# OSSI-1_Side_Panel.net
KiCad netlist of a schematic drawn in EAGLE
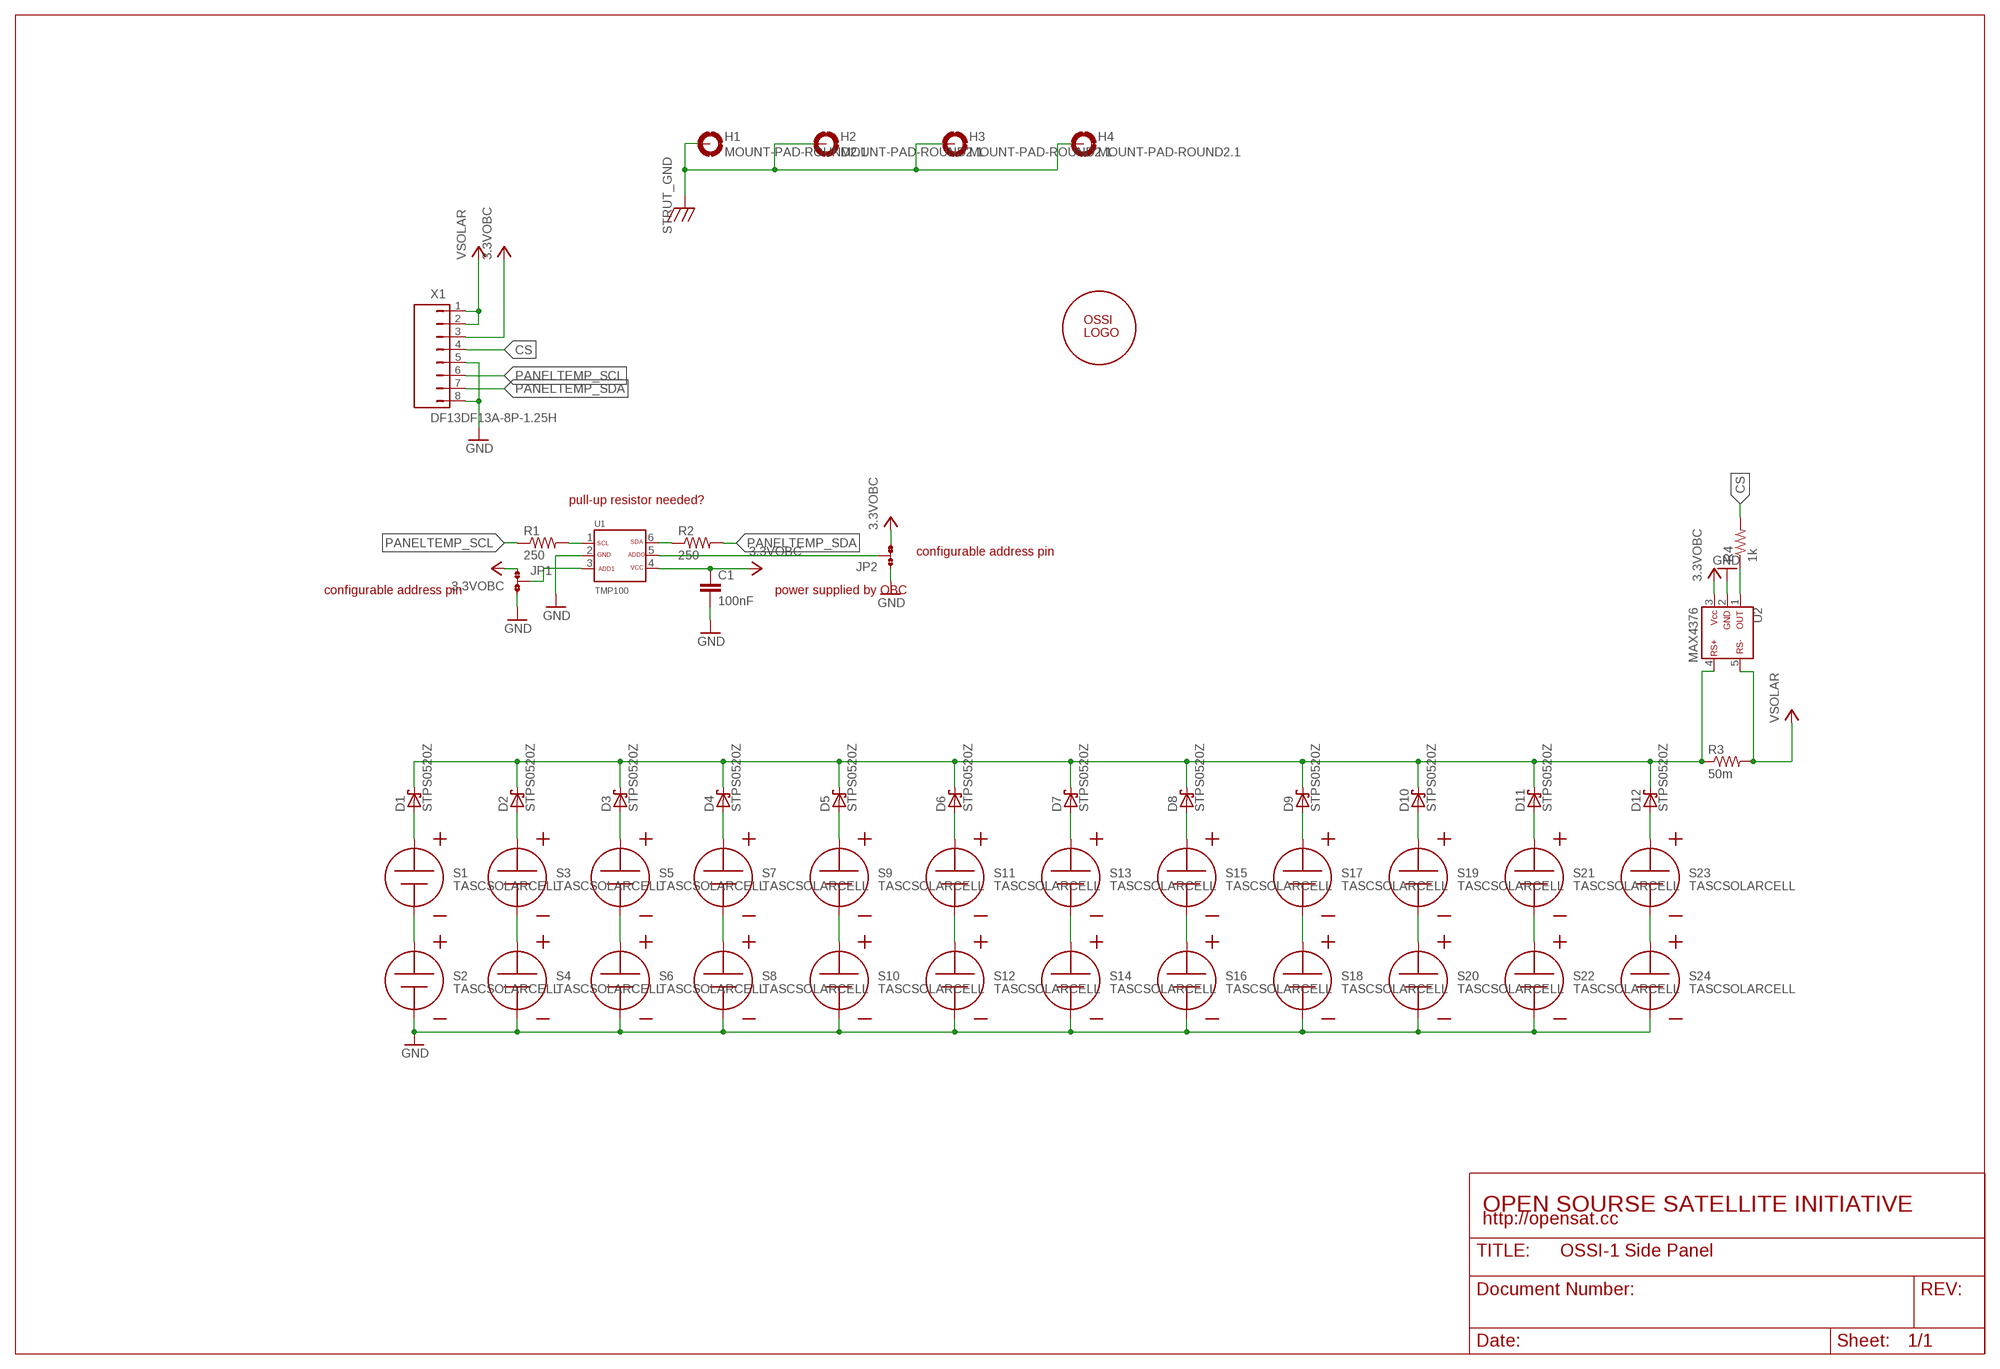
[diagram p0: schematic, sheet 1]

(export (version "E")
  (design (tool "Eeschema 10.0.6"))
  (components
    (comp (ref "C1")
      (value "100nF")
      (footprint "eagle-import:C0603(1608)")
      (libsource (lib "eagle-import") (part "C0603(1608)"))
    )
    (comp (ref "D1")
      (value "STPS0520Z")
      (footprint "eagle-import:SOD-123")
      (libsource (lib "eagle-import") (part "STPS0520Z"))
    )
    (comp (ref "D2")
      (value "STPS0520Z")
      (footprint "eagle-import:SOD-123")
      (libsource (lib "eagle-import") (part "STPS0520Z"))
    )
    (comp (ref "D3")
      (value "STPS0520Z")
      (footprint "eagle-import:SOD-123")
      (libsource (lib "eagle-import") (part "STPS0520Z"))
    )
    (comp (ref "D4")
      (value "STPS0520Z")
      (footprint "eagle-import:SOD-123")
      (libsource (lib "eagle-import") (part "STPS0520Z"))
    )
    (comp (ref "D5")
      (value "STPS0520Z")
      (footprint "eagle-import:SOD-123")
      (libsource (lib "eagle-import") (part "STPS0520Z"))
    )
    (comp (ref "D6")
      (value "STPS0520Z")
      (footprint "eagle-import:SOD-123")
      (libsource (lib "eagle-import") (part "STPS0520Z"))
    )
    (comp (ref "D7")
      (value "STPS0520Z")
      (footprint "eagle-import:SOD-123")
      (libsource (lib "eagle-import") (part "STPS0520Z"))
    )
    (comp (ref "D8")
      (value "STPS0520Z")
      (footprint "eagle-import:SOD-123")
      (libsource (lib "eagle-import") (part "STPS0520Z"))
    )
    (comp (ref "D9")
      (value "STPS0520Z")
      (footprint "eagle-import:SOD-123")
      (libsource (lib "eagle-import") (part "STPS0520Z"))
    )
    (comp (ref "D10")
      (value "STPS0520Z")
      (footprint "eagle-import:SOD-123")
      (libsource (lib "eagle-import") (part "STPS0520Z"))
    )
    (comp (ref "D11")
      (value "STPS0520Z")
      (footprint "eagle-import:SOD-123")
      (libsource (lib "eagle-import") (part "STPS0520Z"))
    )
    (comp (ref "D12")
      (value "STPS0520Z")
      (footprint "eagle-import:SOD-123")
      (libsource (lib "eagle-import") (part "STPS0520Z"))
    )
    (comp (ref "H1")
      (value "MOUNT-PAD-ROUND2.1")
      (footprint "eagle-import:2.1-PAD-ROUND")
      (libsource (lib "eagle-import") (part "MOUNT-PAD-ROUND2.1"))
    )
    (comp (ref "H2")
      (value "MOUNT-PAD-ROUND2.1")
      (footprint "eagle-import:2.1-PAD-ROUND")
      (libsource (lib "eagle-import") (part "MOUNT-PAD-ROUND2.1"))
    )
    (comp (ref "H3")
      (value "MOUNT-PAD-ROUND2.1")
      (footprint "eagle-import:2.1-PAD-ROUND")
      (libsource (lib "eagle-import") (part "MOUNT-PAD-ROUND2.1"))
    )
    (comp (ref "H4")
      (value "MOUNT-PAD-ROUND2.1")
      (footprint "eagle-import:2.1-PAD-ROUND")
      (libsource (lib "eagle-import") (part "MOUNT-PAD-ROUND2.1"))
    )
    (comp (ref "JP1")
      (value "JP2")
      (footprint "eagle-import:JP2SMD0603")
      (libsource (lib "eagle-import") (part "JP2"))
    )
    (comp (ref "JP2")
      (value "JP2")
      (footprint "eagle-import:JP2SMD0603")
      (libsource (lib "eagle-import") (part "JP2"))
    )
    (comp (ref "R1")
      (value "250")
      (footprint "eagle-import:R0603(1608)")
      (libsource (lib "eagle-import") (part "R0603(1608)"))
    )
    (comp (ref "R2")
      (value "250")
      (footprint "eagle-import:R0603(1608)")
      (libsource (lib "eagle-import") (part "R0603(1608)"))
    )
    (comp (ref "R3")
      (value "50m")
      (footprint "eagle-import:WSL1206")
      (libsource (lib "eagle-import") (part "RWSL1206"))
    )
    (comp (ref "R4")
      (value "1k")
      (footprint "eagle-import:R0603(1608)")
      (libsource (lib "eagle-import") (part "R0603(1608)"))
    )
    (comp (ref "S1")
      (value "TASCSOLARCELL")
      (footprint "eagle-import:TASCSOLARCELL")
      (libsource (lib "eagle-import") (part "TASCSOLARCELL"))
    )
    (comp (ref "S2")
      (value "TASCSOLARCELL")
      (footprint "eagle-import:TASCSOLARCELL")
      (libsource (lib "eagle-import") (part "TASCSOLARCELL"))
    )
    (comp (ref "S3")
      (value "TASCSOLARCELL")
      (footprint "eagle-import:TASCSOLARCELL")
      (libsource (lib "eagle-import") (part "TASCSOLARCELL"))
    )
    (comp (ref "S4")
      (value "TASCSOLARCELL")
      (footprint "eagle-import:TASCSOLARCELL")
      (libsource (lib "eagle-import") (part "TASCSOLARCELL"))
    )
    (comp (ref "S5")
      (value "TASCSOLARCELL")
      (footprint "eagle-import:TASCSOLARCELL")
      (libsource (lib "eagle-import") (part "TASCSOLARCELL"))
    )
    (comp (ref "S6")
      (value "TASCSOLARCELL")
      (footprint "eagle-import:TASCSOLARCELL")
      (libsource (lib "eagle-import") (part "TASCSOLARCELL"))
    )
    (comp (ref "S7")
      (value "TASCSOLARCELL")
      (footprint "eagle-import:TASCSOLARCELL")
      (libsource (lib "eagle-import") (part "TASCSOLARCELL"))
    )
    (comp (ref "S8")
      (value "TASCSOLARCELL")
      (footprint "eagle-import:TASCSOLARCELL")
      (libsource (lib "eagle-import") (part "TASCSOLARCELL"))
    )
    (comp (ref "S9")
      (value "TASCSOLARCELL")
      (footprint "eagle-import:TASCSOLARCELL")
      (libsource (lib "eagle-import") (part "TASCSOLARCELL"))
    )
    (comp (ref "S10")
      (value "TASCSOLARCELL")
      (footprint "eagle-import:TASCSOLARCELL")
      (libsource (lib "eagle-import") (part "TASCSOLARCELL"))
    )
    (comp (ref "S11")
      (value "TASCSOLARCELL")
      (footprint "eagle-import:TASCSOLARCELL")
      (libsource (lib "eagle-import") (part "TASCSOLARCELL"))
    )
    (comp (ref "S12")
      (value "TASCSOLARCELL")
      (footprint "eagle-import:TASCSOLARCELL")
      (libsource (lib "eagle-import") (part "TASCSOLARCELL"))
    )
    (comp (ref "S13")
      (value "TASCSOLARCELL")
      (footprint "eagle-import:TASCSOLARCELL")
      (libsource (lib "eagle-import") (part "TASCSOLARCELL"))
    )
    (comp (ref "S14")
      (value "TASCSOLARCELL")
      (footprint "eagle-import:TASCSOLARCELL")
      (libsource (lib "eagle-import") (part "TASCSOLARCELL"))
    )
    (comp (ref "S15")
      (value "TASCSOLARCELL")
      (footprint "eagle-import:TASCSOLARCELL")
      (libsource (lib "eagle-import") (part "TASCSOLARCELL"))
    )
    (comp (ref "S16")
      (value "TASCSOLARCELL")
      (footprint "eagle-import:TASCSOLARCELL")
      (libsource (lib "eagle-import") (part "TASCSOLARCELL"))
    )
    (comp (ref "S17")
      (value "TASCSOLARCELL")
      (footprint "eagle-import:TASCSOLARCELL")
      (libsource (lib "eagle-import") (part "TASCSOLARCELL"))
    )
    (comp (ref "S18")
      (value "TASCSOLARCELL")
      (footprint "eagle-import:TASCSOLARCELL")
      (libsource (lib "eagle-import") (part "TASCSOLARCELL"))
    )
    (comp (ref "S19")
      (value "TASCSOLARCELL")
      (footprint "eagle-import:TASCSOLARCELL")
      (libsource (lib "eagle-import") (part "TASCSOLARCELL"))
    )
    (comp (ref "S20")
      (value "TASCSOLARCELL")
      (footprint "eagle-import:TASCSOLARCELL")
      (libsource (lib "eagle-import") (part "TASCSOLARCELL"))
    )
    (comp (ref "S21")
      (value "TASCSOLARCELL")
      (footprint "eagle-import:TASCSOLARCELL")
      (libsource (lib "eagle-import") (part "TASCSOLARCELL"))
    )
    (comp (ref "S22")
      (value "TASCSOLARCELL")
      (footprint "eagle-import:TASCSOLARCELL")
      (libsource (lib "eagle-import") (part "TASCSOLARCELL"))
    )
    (comp (ref "S23")
      (value "TASCSOLARCELL")
      (footprint "eagle-import:TASCSOLARCELL")
      (libsource (lib "eagle-import") (part "TASCSOLARCELL"))
    )
    (comp (ref "S24")
      (value "TASCSOLARCELL")
      (footprint "eagle-import:TASCSOLARCELL")
      (libsource (lib "eagle-import") (part "TASCSOLARCELL"))
    )
    (comp (ref "U$2")
      (value "OSSILOGO")
      (footprint "eagle-import:OSSILOGORECT1005")
      (libsource (lib "eagle-import") (part "OSSILOGO"))
    )
    (comp (ref "U1")
      (value "TMP100")
      (footprint "eagle-import:SOT23-6DBV")
      (libsource (lib "eagle-import") (part "TMP100"))
    )
    (comp (ref "U2")
      (value "MAX4376")
      (footprint "eagle-import:SOT23-5DBV")
      (libsource (lib "eagle-import") (part "MAX4376"))
    )
    (comp (ref "X1")
      (value "DF13DF13A-8P-1.25H")
      (footprint "eagle-import:DF13A-8P")
      (libsource (lib "eagle-import") (part "DF13DF13A-8P-1.25H"))
    )
  )
  (nets
    (net (code "1") (name "3.3VOBC") (class "Default")
      (node (ref "C1") (pin "1") (pinfunction "1_1") (pintype "passive"))
      (node (ref "JP1") (pin "1") (pinfunction "1_1") (pintype "passive"))
      (node (ref "JP2") (pin "3") (pinfunction "3_3") (pintype "passive"))
      (node (ref "U1") (pin "4") (pinfunction "4_4") (pintype "bidirectional"))
      (node (ref "U2") (pin "3") (pinfunction "P$3_3") (pintype "power_in"))
      (node (ref "X1") (pin "3") (pinfunction "3_3") (pintype "passive"))
    )
    (net (code "2") (name "CS") (class "Default")
      (node (ref "R4") (pin "2") (pinfunction "2_2") (pintype "passive"))
      (node (ref "X1") (pin "4") (pinfunction "4_4") (pintype "passive"))
    )
    (net (code "3") (name "GND") (class "Default")
      (node (ref "C1") (pin "2") (pinfunction "2_2") (pintype "passive"))
      (node (ref "JP1") (pin "3") (pinfunction "3_3") (pintype "passive"))
      (node (ref "JP2") (pin "1") (pinfunction "1_1") (pintype "passive"))
      (node (ref "S10") (pin "N") (pinfunction "N_N") (pintype "power_in"))
      (node (ref "S12") (pin "N") (pinfunction "N_N") (pintype "power_in"))
      (node (ref "S14") (pin "N") (pinfunction "N_N") (pintype "power_in"))
      (node (ref "S16") (pin "N") (pinfunction "N_N") (pintype "power_in"))
      (node (ref "S18") (pin "N") (pinfunction "N_N") (pintype "power_in"))
      (node (ref "S2") (pin "N") (pinfunction "N_N") (pintype "power_in"))
      (node (ref "S20") (pin "N") (pinfunction "N_N") (pintype "power_in"))
      (node (ref "S22") (pin "N") (pinfunction "N_N") (pintype "power_in"))
      (node (ref "S24") (pin "N") (pinfunction "N_N") (pintype "power_in"))
      (node (ref "S4") (pin "N") (pinfunction "N_N") (pintype "power_in"))
      (node (ref "S6") (pin "N") (pinfunction "N_N") (pintype "power_in"))
      (node (ref "S8") (pin "N") (pinfunction "N_N") (pintype "power_in"))
      (node (ref "U1") (pin "2") (pinfunction "2_2") (pintype "bidirectional"))
      (node (ref "U2") (pin "2") (pinfunction "P$2_2") (pintype "power_in"))
      (node (ref "X1") (pin "5") (pinfunction "5_5") (pintype "passive"))
      (node (ref "X1") (pin "8") (pinfunction "8_8") (pintype "passive"))
    )
    (net (code "4") (name "Net-(D1-PadA)") (class "Default")
      (node (ref "D1") (pin "A") (pinfunction "A_A") (pintype "passive"))
      (node (ref "S1") (pin "P") (pinfunction "P_P") (pintype "power_in"))
    )
    (net (code "5") (name "Net-(D2-PadA)") (class "Default")
      (node (ref "D2") (pin "A") (pinfunction "A_A") (pintype "passive"))
      (node (ref "S3") (pin "P") (pinfunction "P_P") (pintype "power_in"))
    )
    (net (code "6") (name "Net-(D3-PadA)") (class "Default")
      (node (ref "D3") (pin "A") (pinfunction "A_A") (pintype "passive"))
      (node (ref "S5") (pin "P") (pinfunction "P_P") (pintype "power_in"))
    )
    (net (code "7") (name "Net-(D4-PadA)") (class "Default")
      (node (ref "D4") (pin "A") (pinfunction "A_A") (pintype "passive"))
      (node (ref "S7") (pin "P") (pinfunction "P_P") (pintype "power_in"))
    )
    (net (code "8") (name "Net-(D5-PadA)") (class "Default")
      (node (ref "D5") (pin "A") (pinfunction "A_A") (pintype "passive"))
      (node (ref "S9") (pin "P") (pinfunction "P_P") (pintype "power_in"))
    )
    (net (code "9") (name "Net-(D6-PadA)") (class "Default")
      (node (ref "D6") (pin "A") (pinfunction "A_A") (pintype "passive"))
      (node (ref "S11") (pin "P") (pinfunction "P_P") (pintype "power_in"))
    )
    (net (code "10") (name "Net-(D7-PadA)") (class "Default")
      (node (ref "D7") (pin "A") (pinfunction "A_A") (pintype "passive"))
      (node (ref "S13") (pin "P") (pinfunction "P_P") (pintype "power_in"))
    )
    (net (code "11") (name "Net-(D8-PadA)") (class "Default")
      (node (ref "D8") (pin "A") (pinfunction "A_A") (pintype "passive"))
      (node (ref "S15") (pin "P") (pinfunction "P_P") (pintype "power_in"))
    )
    (net (code "12") (name "Net-(D9-PadA)") (class "Default")
      (node (ref "D9") (pin "A") (pinfunction "A_A") (pintype "passive"))
      (node (ref "S17") (pin "P") (pinfunction "P_P") (pintype "power_in"))
    )
    (net (code "13") (name "Net-(D10-PadA)") (class "Default")
      (node (ref "D10") (pin "A") (pinfunction "A_A") (pintype "passive"))
      (node (ref "S19") (pin "P") (pinfunction "P_P") (pintype "power_in"))
    )
    (net (code "14") (name "Net-(D11-PadA)") (class "Default")
      (node (ref "D11") (pin "A") (pinfunction "A_A") (pintype "passive"))
      (node (ref "S21") (pin "P") (pinfunction "P_P") (pintype "power_in"))
    )
    (net (code "15") (name "Net-(D12-PadA)") (class "Default")
      (node (ref "D12") (pin "A") (pinfunction "A_A") (pintype "passive"))
      (node (ref "S23") (pin "P") (pinfunction "P_P") (pintype "power_in"))
    )
    (net (code "16") (name "Net-(JP1-Pad2)") (class "Default")
      (node (ref "JP1") (pin "2") (pinfunction "2_2") (pintype "passive"))
      (node (ref "U1") (pin "3") (pinfunction "3_3") (pintype "bidirectional"))
    )
    (net (code "17") (name "Net-(JP2-Pad2)") (class "Default")
      (node (ref "JP2") (pin "2") (pinfunction "2_2") (pintype "passive"))
      (node (ref "U1") (pin "5") (pinfunction "5_5") (pintype "bidirectional"))
    )
    (net (code "18") (name "Net-(R1-Pad2)") (class "Default")
      (node (ref "R1") (pin "2") (pinfunction "2_2") (pintype "passive"))
      (node (ref "U1") (pin "1") (pinfunction "1_1") (pintype "bidirectional"))
    )
    (net (code "19") (name "Net-(R2-Pad1)") (class "Default")
      (node (ref "R2") (pin "1") (pinfunction "1_1") (pintype "passive"))
      (node (ref "U1") (pin "6") (pinfunction "6_6") (pintype "bidirectional"))
    )
    (net (code "20") (name "Net-(R3-1)") (class "Default")
      (node (ref "D1") (pin "C") (pinfunction "C_C") (pintype "passive"))
      (node (ref "D10") (pin "C") (pinfunction "C_C") (pintype "passive"))
      (node (ref "D11") (pin "C") (pinfunction "C_C") (pintype "passive"))
      (node (ref "D12") (pin "C") (pinfunction "C_C") (pintype "passive"))
      (node (ref "D2") (pin "C") (pinfunction "C_C") (pintype "passive"))
      (node (ref "D3") (pin "C") (pinfunction "C_C") (pintype "passive"))
      (node (ref "D4") (pin "C") (pinfunction "C_C") (pintype "passive"))
      (node (ref "D5") (pin "C") (pinfunction "C_C") (pintype "passive"))
      (node (ref "D6") (pin "C") (pinfunction "C_C") (pintype "passive"))
      (node (ref "D7") (pin "C") (pinfunction "C_C") (pintype "passive"))
      (node (ref "D8") (pin "C") (pinfunction "C_C") (pintype "passive"))
      (node (ref "D9") (pin "C") (pinfunction "C_C") (pintype "passive"))
      (node (ref "R3") (pin "P$1") (pinfunction "1_P$1") (pintype "passive"))
      (node (ref "U2") (pin "4") (pinfunction "P$4_4") (pintype "input"))
    )
    (net (code "21") (name "Net-(S1-PadN)") (class "Default")
      (node (ref "S1") (pin "N") (pinfunction "N_N") (pintype "power_in"))
      (node (ref "S2") (pin "P") (pinfunction "P_P") (pintype "power_in"))
    )
    (net (code "22") (name "Net-(S3-PadN)") (class "Default")
      (node (ref "S3") (pin "N") (pinfunction "N_N") (pintype "power_in"))
      (node (ref "S4") (pin "P") (pinfunction "P_P") (pintype "power_in"))
    )
    (net (code "23") (name "Net-(S5-PadN)") (class "Default")
      (node (ref "S5") (pin "N") (pinfunction "N_N") (pintype "power_in"))
      (node (ref "S6") (pin "P") (pinfunction "P_P") (pintype "power_in"))
    )
    (net (code "24") (name "Net-(S7-PadN)") (class "Default")
      (node (ref "S7") (pin "N") (pinfunction "N_N") (pintype "power_in"))
      (node (ref "S8") (pin "P") (pinfunction "P_P") (pintype "power_in"))
    )
    (net (code "25") (name "Net-(S10-PadP)") (class "Default")
      (node (ref "S10") (pin "P") (pinfunction "P_P") (pintype "power_in"))
      (node (ref "S9") (pin "N") (pinfunction "N_N") (pintype "power_in"))
    )
    (net (code "26") (name "Net-(S11-PadN)") (class "Default")
      (node (ref "S11") (pin "N") (pinfunction "N_N") (pintype "power_in"))
      (node (ref "S12") (pin "P") (pinfunction "P_P") (pintype "power_in"))
    )
    (net (code "27") (name "Net-(S13-PadN)") (class "Default")
      (node (ref "S13") (pin "N") (pinfunction "N_N") (pintype "power_in"))
      (node (ref "S14") (pin "P") (pinfunction "P_P") (pintype "power_in"))
    )
    (net (code "28") (name "Net-(S15-PadN)") (class "Default")
      (node (ref "S15") (pin "N") (pinfunction "N_N") (pintype "power_in"))
      (node (ref "S16") (pin "P") (pinfunction "P_P") (pintype "power_in"))
    )
    (net (code "29") (name "Net-(S17-PadN)") (class "Default")
      (node (ref "S17") (pin "N") (pinfunction "N_N") (pintype "power_in"))
      (node (ref "S18") (pin "P") (pinfunction "P_P") (pintype "power_in"))
    )
    (net (code "30") (name "Net-(S19-PadN)") (class "Default")
      (node (ref "S19") (pin "N") (pinfunction "N_N") (pintype "power_in"))
      (node (ref "S20") (pin "P") (pinfunction "P_P") (pintype "power_in"))
    )
    (net (code "31") (name "Net-(S21-PadN)") (class "Default")
      (node (ref "S21") (pin "N") (pinfunction "N_N") (pintype "power_in"))
      (node (ref "S22") (pin "P") (pinfunction "P_P") (pintype "power_in"))
    )
    (net (code "32") (name "Net-(S23-PadN)") (class "Default")
      (node (ref "S23") (pin "N") (pinfunction "N_N") (pintype "power_in"))
      (node (ref "S24") (pin "P") (pinfunction "P_P") (pintype "power_in"))
    )
    (net (code "33") (name "Net-(U2-P$1)") (class "Default")
      (node (ref "R4") (pin "1") (pinfunction "1_1") (pintype "passive"))
      (node (ref "U2") (pin "1") (pinfunction "P$1_1") (pintype "output"))
    )
    (net (code "34") (name "PANELTEMP_SCL") (class "Default")
      (node (ref "R1") (pin "1") (pinfunction "1_1") (pintype "passive"))
      (node (ref "X1") (pin "6") (pinfunction "6_6") (pintype "passive"))
    )
    (net (code "35") (name "PANELTEMP_SDA") (class "Default")
      (node (ref "R2") (pin "2") (pinfunction "2_2") (pintype "passive"))
      (node (ref "X1") (pin "7") (pinfunction "7_7") (pintype "passive"))
    )
    (net (code "36") (name "STRUT_GND") (class "Default")
      (node (ref "H1") (pin "B3,2") (pinfunction "MOUNT_B3,2") (pintype "passive"))
      (node (ref "H2") (pin "B3,2") (pinfunction "MOUNT_B3,2") (pintype "passive"))
      (node (ref "H3") (pin "B3,2") (pinfunction "MOUNT_B3,2") (pintype "passive"))
      (node (ref "H4") (pin "B3,2") (pinfunction "MOUNT_B3,2") (pintype "passive"))
    )
    (net (code "37") (name "VSOLAR") (class "Default")
      (node (ref "R3") (pin "P$2") (pinfunction "2_P$2") (pintype "passive"))
      (node (ref "U2") (pin "5") (pinfunction "P$5_5") (pintype "input"))
      (node (ref "X1") (pin "1") (pinfunction "1_1") (pintype "passive"))
      (node (ref "X1") (pin "2") (pinfunction "2_2") (pintype "passive"))
    )
  )
)
